# Schematic.net
KiCad netlist of a schematic drawn in EAGLE
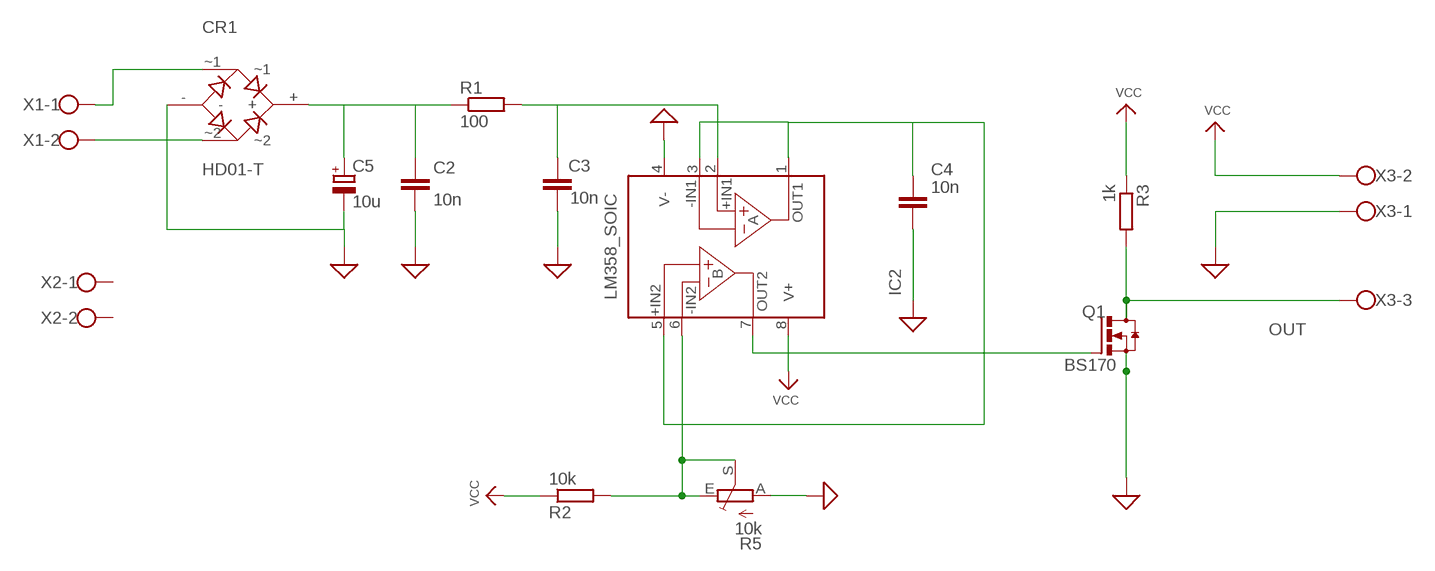
[diagram p0: schematic, sheet 1]

(export (version "E")
  (design (tool "Eeschema 10.0.6"))
  (components
    (comp (ref "C2")
      (value "10n")
      (footprint "eagle-import:CAPC1608X85")
      (libsource (lib "eagle-import") (part "CCHIP-0603(1608-METRIC)_"))
    )
    (comp (ref "C3")
      (value "10n")
      (footprint "eagle-import:CAPC1608X85")
      (libsource (lib "eagle-import") (part "CCHIP-0603(1608-METRIC)_"))
    )
    (comp (ref "C4")
      (value "10n")
      (footprint "eagle-import:CAPC1608X85")
      (libsource (lib "eagle-import") (part "CCHIP-0603(1608-METRIC)_"))
    )
    (comp (ref "C5")
      (value "10u")
      (footprint "eagle-import:140CLH-1010")
      (libsource (lib "eagle-import") (part "CPOL-EU140CLH-1010"))
    )
    (comp (ref "CR1")
      (value "HD01-T")
      (footprint "eagle-import:HD01-T")
      (fields (field (name "MANUFACTURER") "Diodes Incorporated") (field (name "CREATED_BY") "PCBLayout.com"))
      (libsource (lib "eagle-import") (part "HD01-T"))
    )
    (comp (ref "IC2")
      (value "LM358_SOIC")
      (footprint "eagle-import:SOIC127P600X175-8N")
      (fields (field (name "MANUFACTURER") "Generic"))
      (libsource (lib "eagle-import") (part "LM358_SOIC"))
    )
    (comp (ref "Q1")
      (value "BS170")
      (footprint "eagle-import:TO92-3")
      (fields
        (field (name "DIGIKEY_PART_NUMBER") "2156-BS170-ND")
        (field (name "MANUFACTURER") "Fairchild Semiconductor")
        (field (name "CREATED_BY") "PCBLayout.com")
      )
      (libsource (lib "eagle-import") (part "BS170"))
    )
    (comp (ref "R1")
      (value "100")
      (footprint "eagle-import:R0603")
      (libsource (lib "eagle-import") (part "R-EU_R0603"))
    )
    (comp (ref "R2")
      (value "10k")
      (footprint "eagle-import:R0603")
      (libsource (lib "eagle-import") (part "R-EU_R0603"))
    )
    (comp (ref "R3")
      (value "1k")
      (footprint "eagle-import:R0603")
      (libsource (lib "eagle-import") (part "R-EU_R0603"))
    )
    (comp (ref "R5")
      (value "10k")
      (footprint "eagle-import:SP19L")
      (libsource (lib "eagle-import") (part "TRIM_EU-B90P"))
    )
    (comp (ref "X1")
      (value "W237-102")
      (footprint "eagle-import:W237-102")
      (fields (field (name "MPN") "237-102"))
      (libsource (lib "eagle-import") (part "W237-102"))
    )
    (comp (ref "X2")
      (value "W237-102")
      (footprint "eagle-import:W237-102")
      (fields (field (name "MPN") "237-102"))
      (libsource (lib "eagle-import") (part "W237-102"))
    )
    (comp (ref "X3")
      (value "W237-103")
      (footprint "eagle-import:W237-103")
      (fields (field (name "MPN") "237-103"))
      (libsource (lib "eagle-import") (part "W237-103"))
    )
  )
  (nets
    (net (code "1") (name "/OUT") (class "Default")
      (node (ref "Q1") (pin "1") (pinfunction "D_1") (pintype "passive"))
      (node (ref "R3") (pin "2") (pinfunction "2_2") (pintype "passive"))
      (node (ref "X3") (pin "3") (pinfunction "KL_3") (pintype "passive"))
    )
    (net (code "2") (name "Net-(C2-Pad1)") (class "Default")
      (node (ref "C2") (pin "1") (pinfunction "1_1") (pintype "passive"))
      (node (ref "C5") (pin "+") (pinfunction "+_+") (pintype "passive"))
      (node (ref "CR1") (pin "+") (pinfunction "+_+") (pintype "passive"))
      (node (ref "R1") (pin "1") (pinfunction "1_1") (pintype "passive"))
    )
    (net (code "3") (name "Net-(CR1-~{1})") (class "Default")
      (node (ref "CR1") (pin "~1") (pinfunction "~{1}_~1") (pintype "passive"))
      (node (ref "X1") (pin "1") (pinfunction "KL_1") (pintype "passive"))
    )
    (net (code "4") (name "Net-(CR1-~{2})") (class "Default")
      (node (ref "CR1") (pin "~2") (pinfunction "~{2}_~2") (pintype "passive"))
      (node (ref "X1") (pin "2") (pinfunction "KL_2") (pintype "passive"))
    )
    (net (code "5") (name "Net-(IC2-+IN1)") (class "Default")
      (node (ref "C4") (pin "1") (pinfunction "1_1") (pintype "passive"))
      (node (ref "IC2") (pin "1") (pinfunction "OUT1_1") (pintype "passive"))
      (node (ref "IC2") (pin "3") (pinfunction "+IN1_3") (pintype "input"))
      (node (ref "IC2") (pin "5") (pinfunction "+IN2_5") (pintype "passive"))
    )
    (net (code "6") (name "Net-(IC2--IN1)") (class "Default")
      (node (ref "C3") (pin "1") (pinfunction "1_1") (pintype "passive"))
      (node (ref "IC2") (pin "2") (pinfunction "-IN1_2") (pintype "input"))
      (node (ref "R1") (pin "2") (pinfunction "2_2") (pintype "passive"))
    )
    (net (code "7") (name "Net-(IC2--IN2)") (class "Default")
      (node (ref "IC2") (pin "6") (pinfunction "-IN2_6") (pintype "passive"))
      (node (ref "R2") (pin "2") (pinfunction "2_2") (pintype "passive"))
      (node (ref "R5") (pin "E") (pinfunction "E_E") (pintype "passive"))
      (node (ref "R5") (pin "S") (pinfunction "S_S") (pintype "passive"))
    )
    (net (code "8") (name "Net-(IC2-OUT2)") (class "Default")
      (node (ref "IC2") (pin "7") (pinfunction "OUT2_7") (pintype "passive"))
      (node (ref "Q1") (pin "2") (pinfunction "G_2") (pintype "passive"))
    )
    (net (code "9") (name "SUP") (class "Default")
      (node (ref "C2") (pin "2") (pinfunction "2_2") (pintype "passive"))
      (node (ref "C3") (pin "2") (pinfunction "2_2") (pintype "passive"))
      (node (ref "C4") (pin "2") (pinfunction "2_2") (pintype "passive"))
      (node (ref "C5") (pin "-") (pinfunction "-_-") (pintype "passive"))
      (node (ref "CR1") (pin "-") (pinfunction "-_-") (pintype "passive"))
      (node (ref "IC2") (pin "4") (pinfunction "V-_4") (pintype "bidirectional"))
      (node (ref "Q1") (pin "3") (pinfunction "S_3") (pintype "passive"))
      (node (ref "R5") (pin "A") (pinfunction "A_A") (pintype "passive"))
      (node (ref "X3") (pin "1") (pinfunction "KL_1") (pintype "passive"))
    )
    (net (code "10") (name "VCC") (class "Default")
      (node (ref "IC2") (pin "8") (pinfunction "V+_8") (pintype "bidirectional"))
      (node (ref "R2") (pin "1") (pinfunction "1_1") (pintype "passive"))
      (node (ref "R3") (pin "1") (pinfunction "1_1") (pintype "passive"))
      (node (ref "X3") (pin "2") (pinfunction "KL_2") (pintype "passive"))
    )
    (net (code "11") (name "unconnected-(X2A-KL-Pad1)") (class "Default")
      (node (ref "X2") (pin "1") (pinfunction "KL_1") (pintype "passive"))
    )
    (net (code "12") (name "unconnected-(X2B-KL-Pad2)") (class "Default")
      (node (ref "X2") (pin "2") (pinfunction "KL_2") (pintype "passive"))
    )
  )
)
